# HLK-AX3000-KIT-POWER_LED.net
KiCad netlist of a schematic drawn in Altium Designer
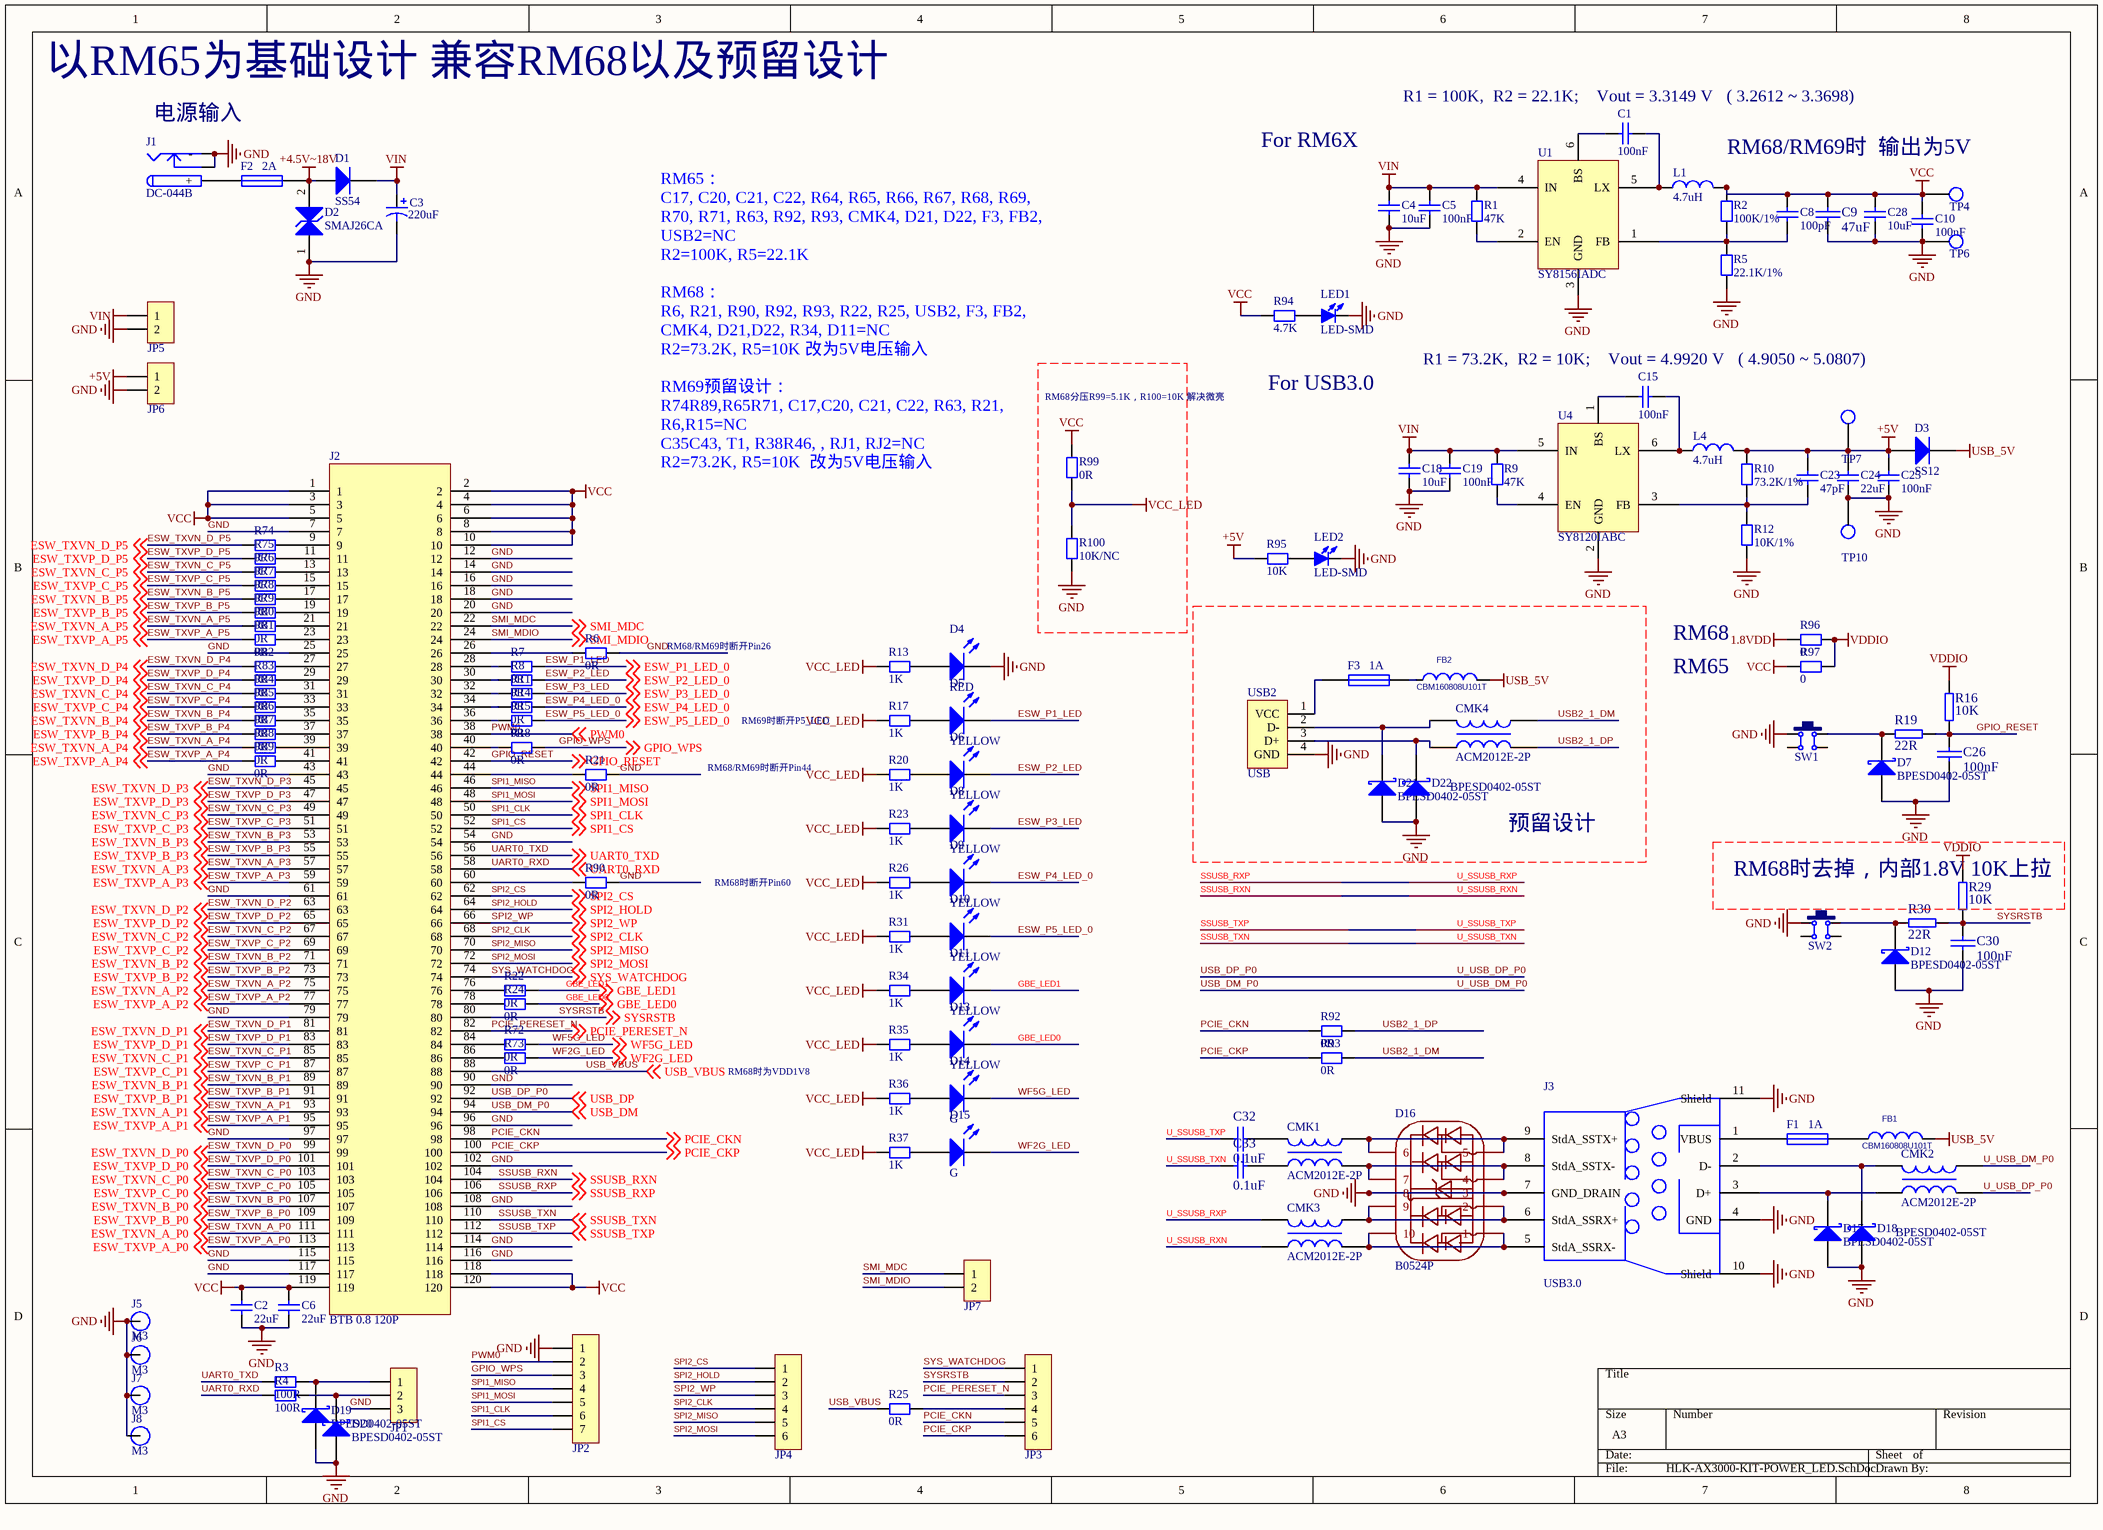
[diagram p0: HLK-AX3000-KIT-POWER_LED.SchDoc]

(export (version "E")
  (design (tool "Eeschema 10.0.6"))
  (components
    (comp (ref "C1")
      (value "100nF")
      (footprint "C 0402_L")
      (description "Capacitor")
      (libsource (lib "LORATEMPSENSOR_V0.02") (part "Cap"))
    )
    (comp (ref "C2")
      (value "22uF")
      (footprint "C 0805_L")
      (description "Capacitor")
      (fields
        (field (name "MANUFACTURER") "Generic Components")
        (field (name "PUBLISHER") "Altium Hobart Technology Centre")
      )
      (libsource (lib "*") (part "Cap"))
    )
    (comp (ref "C3")
      (value "220uF")
      (footprint "CT 8*12 - C")
      (description "Polarized Capacitor (Radial)")
      (fields (field (name "PUBLISHER") "Altium Limited"))
      (libsource (lib "Miscellaneous Devices") (part "Cap Pol1"))
    )
    (comp (ref "C4")
      (value "10uF")
      (footprint "C 0805_L")
      (description "Capacitor")
      (fields
        (field (name "MANUFACTURER") "Generic Components")
        (field (name "PUBLISHER") "Altium Hobart Technology Centre")
      )
      (libsource (lib "*") (part "Cap"))
    )
    (comp (ref "C5")
      (value "100nF")
      (footprint "C 0402_L")
      (description "Capacitor")
      (libsource (lib "LORATEMPSENSOR_V0.02") (part "Cap"))
    )
    (comp (ref "C6")
      (value "22uF")
      (footprint "C 0805_L")
      (description "Capacitor")
      (fields
        (field (name "MANUFACTURER") "Generic Components")
        (field (name "PUBLISHER") "Altium Hobart Technology Centre")
      )
      (libsource (lib "*") (part "Cap"))
    )
    (comp (ref "C8")
      (value "100pF")
      (footprint "C 0402_L")
      (description "Capacitor")
      (fields
        (field (name "MANUFACTURER") "Generic Components")
        (field (name "PUBLISHER") "Altium Hobart Technology Centre")
      )
      (libsource (lib "*") (part "Cap"))
    )
    (comp (ref "C9")
      (value "47uF")
      (footprint "C 1206_L")
      (description "Capacitor")
      (libsource (lib "*") (part "CAP"))
    )
    (comp (ref "C10")
      (value "100nF")
      (footprint "C 0402_L")
      (description "Capacitor")
      (libsource (lib "LORATEMPSENSOR_V0.02") (part "Cap"))
    )
    (comp (ref "C15")
      (value "100nF")
      (footprint "C 0402_L")
      (description "Capacitor")
      (libsource (lib "LORATEMPSENSOR_V0.02") (part "Cap"))
    )
    (comp (ref "C18")
      (value "10uF")
      (footprint "C 0805_L")
      (description "Capacitor")
      (fields
        (field (name "MANUFACTURER") "Generic Components")
        (field (name "PUBLISHER") "Altium Hobart Technology Centre")
      )
      (libsource (lib "*") (part "Cap"))
    )
    (comp (ref "C19")
      (value "100nF")
      (footprint "C 0402_L")
      (description "Capacitor")
      (libsource (lib "LORATEMPSENSOR_V0.02") (part "Cap"))
    )
    (comp (ref "C23")
      (value "47pF")
      (footprint "C 0402_L")
      (description "Capacitor")
      (fields
        (field (name "MANUFACTURER") "Generic Components")
        (field (name "PUBLISHER") "Altium Hobart Technology Centre")
      )
      (libsource (lib "*") (part "Cap"))
    )
    (comp (ref "C24")
      (value "22uF")
      (footprint "C 0805_L")
      (description "Capacitor")
      (fields
        (field (name "MANUFACTURER") "Generic Components")
        (field (name "PUBLISHER") "Altium Hobart Technology Centre")
      )
      (libsource (lib "*") (part "Cap"))
    )
    (comp (ref "C25")
      (value "100nF")
      (footprint "C 0402_L")
      (description "Capacitor")
      (libsource (lib "LORATEMPSENSOR_V0.02") (part "Cap"))
    )
    (comp (ref "C26")
      (value "100nF")
      (footprint "C 0402_L")
      (description "Capacitor")
      (libsource (lib "*") (part "CAP"))
    )
    (comp (ref "C28")
      (value "10uF")
      (footprint "C 0603_L")
      (description "Capacitor")
      (libsource (lib "LORATEMPSENSOR_V0.02") (part "Cap"))
    )
    (comp (ref "C30")
      (value "100nF")
      (footprint "C 0402_L")
      (description "Capacitor")
      (libsource (lib "*") (part "CAP"))
    )
    (comp (ref "C32")
      (value "0.1uF")
      (footprint "C 0402_L")
      (description "Capacitor")
      (libsource (lib "*") (part "CAP"))
    )
    (comp (ref "C33")
      (value "0.1uF")
      (footprint "C 0402_L")
      (description "Capacitor")
      (libsource (lib "*") (part "CAP"))
    )
    (comp (ref "CMK1") (value "ACM2012E-2P") (footprint "SMD_4P") (libsource (lib "*") (part "CMK1")))
    (comp (ref "CMK2") (value "ACM2012E-2P") (footprint "SMD_4P") (libsource (lib "*") (part "CMK1")))
    (comp (ref "CMK3") (value "ACM2012E-2P") (footprint "SMD_4P") (libsource (lib "*") (part "CMK1")))
    (comp (ref "CMK4") (value "ACM2012E-2P") (footprint "SMD_4P_2.1X2.1") (libsource (lib "*") (part "CMK1")))
    (comp (ref "D1")
      (value "SS54")
      (footprint "SMB")
      (description "Default Diode")
      (fields (field (name "PUBLISHER") "Altium Limited"))
      (libsource (lib "Miscellaneous Devices") (part "Diode"))
    )
    (comp (ref "D2") (value "SMAJ26CA") (footprint "DO-214AC") (libsource (lib "My Schlib") (part "TVS")))
    (comp (ref "D3")
      (value "SS12")
      (footprint "SMA")
      (description "Default Diode")
      (fields (field (name "PUBLISHER") "Altium Limited"))
      (libsource (lib "Miscellaneous Devices") (part "Diode"))
    )
    (comp (ref "D4")
      (value "RED")
      (footprint "LED 3MM-R")
      (description "贴片发光二极管")
      (fields (field (name "PUBLISHER") "Altium Limited"))
      (libsource (lib "LORATEMPSENSOR_V0.02") (part "LED0"))
    )
    (comp (ref "D5")
      (value "YELLOW")
      (footprint "LED 3MM-Y")
      (description "贴片发光二极管")
      (fields (field (name "PUBLISHER") "Altium Limited"))
      (libsource (lib "LORATEMPSENSOR_V0.02") (part "LED0"))
    )
    (comp (ref "D6")
      (value "YELLOW")
      (footprint "LED 3MM-Y")
      (description "贴片发光二极管")
      (fields (field (name "PUBLISHER") "Altium Limited"))
      (libsource (lib "LORATEMPSENSOR_V0.02") (part "LED0"))
    )
    (comp (ref "D7")
      (value "BPESD0402-05ST")
      (footprint "esd0402")
      (description "Silicon AF Schottky Diode for High-Speed Switching")
      (fields (field (name "PUBLISHER") "Altium Limited"))
      (libsource (lib "Miscellaneous Devices") (part "Diode BAS70"))
    )
    (comp (ref "D8")
      (value "YELLOW")
      (footprint "LED 3MM-Y")
      (description "贴片发光二极管")
      (fields (field (name "PUBLISHER") "Altium Limited"))
      (libsource (lib "LORATEMPSENSOR_V0.02") (part "LED0"))
    )
    (comp (ref "D9")
      (value "YELLOW")
      (footprint "LED 3MM-Y")
      (description "贴片发光二极管")
      (fields (field (name "PUBLISHER") "Altium Limited"))
      (libsource (lib "LORATEMPSENSOR_V0.02") (part "LED0"))
    )
    (comp (ref "D10")
      (value "YELLOW")
      (footprint "LED 3MM-Y")
      (description "贴片发光二极管")
      (fields (field (name "PUBLISHER") "Altium Limited"))
      (libsource (lib "LORATEMPSENSOR_V0.02") (part "LED0"))
    )
    (comp (ref "D11")
      (value "YELLOW")
      (footprint "LED 3MM-Y")
      (description "贴片发光二极管")
      (fields (field (name "PUBLISHER") "Altium Limited"))
      (libsource (lib "LORATEMPSENSOR_V0.02") (part "LED0"))
    )
    (comp (ref "D12")
      (value "BPESD0402-05ST")
      (footprint "esd0402")
      (description "Silicon AF Schottky Diode for High-Speed Switching")
      (fields (field (name "PUBLISHER") "Altium Limited"))
      (libsource (lib "Miscellaneous Devices") (part "Diode BAS70"))
    )
    (comp (ref "D13")
      (value "YELLOW")
      (footprint "LED 3MM-Y")
      (description "贴片发光二极管")
      (fields (field (name "PUBLISHER") "Altium Limited"))
      (libsource (lib "LORATEMPSENSOR_V0.02") (part "LED0"))
    )
    (comp (ref "D14")
      (value "G")
      (footprint "LED 3MM-G")
      (description "贴片发光二极管")
      (fields (field (name "PUBLISHER") "Altium Limited"))
      (libsource (lib "LORATEMPSENSOR_V0.02") (part "LED0"))
    )
    (comp (ref "D15")
      (value "G")
      (footprint "LED 3MM-G")
      (description "贴片发光二极管")
      (fields (field (name "PUBLISHER") "Altium Limited"))
      (libsource (lib "LORATEMPSENSOR_V0.02") (part "LED0"))
    )
    (comp (ref "D16") (value "B0524P") (footprint "DFN-10") (libsource (lib "MY SCHLIB") (part "B0524P")))
    (comp (ref "D17")
      (value "BPESD0402-05ST")
      (footprint "ESD0402")
      (description "Silicon AF Schottky Diode for High-Speed Switching")
      (fields (field (name "PUBLISHER") "Altium Limited"))
      (libsource (lib "Miscellaneous Devices") (part "Diode BAS70"))
    )
    (comp (ref "D18")
      (value "BPESD0402-05ST")
      (footprint "ESD0402")
      (description "Silicon AF Schottky Diode for High-Speed Switching")
      (fields (field (name "PUBLISHER") "Altium Limited"))
      (libsource (lib "Miscellaneous Devices") (part "Diode BAS70"))
    )
    (comp (ref "D19")
      (value "BPESD0402-05ST")
      (footprint "esd0402")
      (description "Silicon AF Schottky Diode for High-Speed Switching")
      (fields (field (name "PUBLISHER") "Altium Limited"))
      (libsource (lib "Miscellaneous Devices") (part "Diode BAS70"))
    )
    (comp (ref "D20")
      (value "BPESD0402-05ST")
      (footprint "esd0402")
      (description "Silicon AF Schottky Diode for High-Speed Switching")
      (fields (field (name "PUBLISHER") "Altium Limited"))
      (libsource (lib "Miscellaneous Devices") (part "Diode BAS70"))
    )
    (comp (ref "D21")
      (value "BPESD0402-05ST")
      (footprint "ESD0402")
      (description "Silicon AF Schottky Diode for High-Speed Switching")
      (fields (field (name "PUBLISHER") "Altium Limited"))
      (libsource (lib "Miscellaneous Devices") (part "Diode BAS70"))
    )
    (comp (ref "D22")
      (value "BPESD0402-05ST")
      (footprint "ESD0402")
      (description "Silicon AF Schottky Diode for High-Speed Switching")
      (fields (field (name "PUBLISHER") "Altium Limited"))
      (libsource (lib "Miscellaneous Devices") (part "Diode BAS70"))
    )
    (comp (ref "F1")
      (value "1A")
      (footprint "FU 0603")
      (description "Fuse")
      (fields (field (name "PUBLISHER") "Altium Limited"))
      (libsource (lib "Miscellaneous Devices") (part "Fuse 1"))
    )
    (comp (ref "F2")
      (value "2A")
      (footprint "FU 1206")
      (description "Fuse")
      (fields (field (name "PUBLISHER") "Altium Limited"))
      (libsource (lib "Miscellaneous Devices") (part "Fuse 1"))
    )
    (comp (ref "F3")
      (value "1A")
      (footprint "FU 0603")
      (description "Fuse")
      (fields (field (name "PUBLISHER") "Altium Limited"))
      (libsource (lib "Miscellaneous Devices") (part "Fuse 1"))
    )
    (comp (ref "FB1") (value "CBM160808U101T") (footprint "L 0603") (libsource (lib "*") (part "INDUCTOR")))
    (comp (ref "FB2") (value "CBM160808U101T") (footprint "L 0603") (libsource (lib "*") (part "INDUCTOR")))
    (comp (ref "J1")
      (value "DC-044B")
      (footprint "DC-005")
      (description "Low Voltage Power Supply Connector")
      (fields (field (name "PUBLISHER") "Altium Limited"))
      (libsource (lib "封装") (part "DC-044B"))
    )
    (comp (ref "J2")
      (value "BTB 0.8 120P")
      (footprint "HLK-RM65")
      (libsource (lib "4.15 - 板对板连接器") (part "BTB 0.8 120P"))
    )
    (comp (ref "J3")
      (value "USB3.0")
      (footprint "USB3.0-9P-DIP")
      (libsource (lib "MY SCHLIB") (part "USB3.0"))
    )
    (comp (ref "J5")
      (value "M3")
      (footprint "M3 125X200")
      (description "铜柱孔")
      (fields (field (name "版权归属") "源创客"))
      (libsource (lib "15.1 - 定位孔-焊盘") (part "M3"))
    )
    (comp (ref "J6")
      (value "M3")
      (footprint "M3 125X200")
      (description "铜柱孔")
      (fields (field (name "版权归属") "源创客"))
      (libsource (lib "15.1 - 定位孔-焊盘") (part "M3"))
    )
    (comp (ref "J7")
      (value "M3")
      (footprint "M3 125X200")
      (description "铜柱孔")
      (fields (field (name "版权归属") "源创客"))
      (libsource (lib "15.1 - 定位孔-焊盘") (part "M3"))
    )
    (comp (ref "J8")
      (value "M3")
      (footprint "M3 125X200")
      (description "铜柱孔")
      (fields (field (name "版权归属") "源创客"))
      (libsource (lib "15.1 - 定位孔-焊盘") (part "M3"))
    )
    (comp (ref "JP1")
      (value "HDR-1X3")
      (footprint "HDR2.54-LI-3P")
      (description "3P接插件")
      (fields (field (name "版权归属") "源创客"))
      (libsource (lib "4.5   - 接插件-脚距2.54") (part "Header 3"))
    )
    (comp (ref "JP2")
      (value "HDR-1X7")
      (footprint "HDR2.54-LI-7P")
      (description "7P接插件")
      (fields (field (name "版权归属") "源创客"))
      (libsource (lib "4.5   - 接插件-脚距2.54") (part "Header 7"))
    )
    (comp (ref "JP3")
      (value "HDR-1X6")
      (footprint "HDR2.54-LI-6P")
      (description "6P接插件")
      (fields (field (name "版权归属") "源创客"))
      (libsource (lib "4.5   - 接插件-脚距2.54") (part "Header 6"))
    )
    (comp (ref "JP4")
      (value "HDR-1X6")
      (footprint "HDR2.54-LI-6P")
      (description "6P接插件")
      (fields (field (name "版权归属") "源创客"))
      (libsource (lib "4.5   - 接插件-脚距2.54") (part "Header 6"))
    )
    (comp (ref "JP5")
      (value "HDR-1X2")
      (footprint "XH2.54-LI-2P")
      (description "2P接插件")
      (fields (field (name "版权归属") "源创客"))
      (libsource (lib "4.5   - 接插件-脚距2.54") (part "Header 2"))
    )
    (comp (ref "JP6")
      (value "HDR-1X2")
      (footprint "XH2.54-LI-2P")
      (description "2P接插件")
      (fields (field (name "版权归属") "源创客"))
      (libsource (lib "4.5   - 接插件-脚距2.54") (part "Header 2"))
    )
    (comp (ref "JP7")
      (value "HDR-1X2")
      (footprint "HDR2.54-LI-2P")
      (description "2P接插件")
      (fields (field (name "版权归属") "源创客"))
      (libsource (lib "4.5   - 接插件-脚距2.54") (part "Header 2"))
    )
    (comp (ref "L1") (value "4.7uH") (footprint "L 6*6") (libsource (lib "封装") (part "LineInductors")))
    (comp (ref "L4") (value "4.7uH") (footprint "L 4*4") (libsource (lib "封装") (part "LineInductors")))
    (comp (ref "LED1")
      (value "LED-SMD")
      (footprint "LED 0603G-L")
      (description "贴片LED")
      (fields (field (name "版权归属") "源创客"))
      (libsource (lib "9.1   - LED") (part "LED-SMD"))
    )
    (comp (ref "LED2")
      (value "LED-SMD")
      (footprint "LED 0603G-L")
      (description "贴片LED")
      (fields (field (name "版权归属") "源创客"))
      (libsource (lib "9.1   - LED") (part "LED-SMD"))
    )
    (comp (ref "R1")
      (value "47K")
      (footprint "R 0402_L")
      (description "贴片电阻")
      (fields (field (name "版权归属") "源创客"))
      (libsource (lib "3.1   - 电阻-电容-电感") (part "R"))
    )
    (comp (ref "R2")
      (value "100K/1%")
      (footprint "R 0402_L")
      (description "贴片电阻")
      (fields (field (name "版权归属") "源创客"))
      (libsource (lib "3.1   - 电阻-电容-电感") (part "R"))
    )
    (comp (ref "R3")
      (value "100R")
      (footprint "R 0402_L")
      (description "贴片电阻")
      (fields (field (name "版权归属") "源创客"))
      (libsource (lib "3.1   - 电阻-电容-电感") (part "R"))
    )
    (comp (ref "R4")
      (value "100R")
      (footprint "R 0402_L")
      (description "贴片电阻")
      (fields (field (name "版权归属") "源创客"))
      (libsource (lib "3.1   - 电阻-电容-电感") (part "R"))
    )
    (comp (ref "R5")
      (value "22.1K/1%")
      (footprint "R 0402_L")
      (description "贴片电阻")
      (fields (field (name "版权归属") "源创客"))
      (libsource (lib "3.1   - 电阻-电容-电感") (part "R"))
    )
    (comp (ref "R6")
      (value "0R")
      (footprint "R 0402_L")
      (description "贴片电阻")
      (fields (field (name "版权归属") "源创客"))
      (libsource (lib "3.1   - 电阻-电容-电感") (part "R"))
    )
    (comp (ref "R7")
      (value "0R")
      (footprint "R 0402_L")
      (description "贴片电阻")
      (fields (field (name "版权归属") "源创客"))
      (libsource (lib "3.1   - 电阻-电容-电感") (part "R"))
    )
    (comp (ref "R8")
      (value "0R")
      (footprint "R 0402_L")
      (description "贴片电阻")
      (fields (field (name "版权归属") "源创客"))
      (libsource (lib "3.1   - 电阻-电容-电感") (part "R"))
    )
    (comp (ref "R9")
      (value "47K")
      (footprint "R 0402_L")
      (description "贴片电阻")
      (fields (field (name "版权归属") "源创客"))
      (libsource (lib "3.1   - 电阻-电容-电感") (part "R"))
    )
    (comp (ref "R10")
      (value "73.2K/1%")
      (footprint "R 0402_L")
      (description "贴片电阻")
      (fields (field (name "版权归属") "源创客"))
      (libsource (lib "3.1   - 电阻-电容-电感") (part "R"))
    )
    (comp (ref "R11")
      (value "0R")
      (footprint "R 0402_L")
      (description "贴片电阻")
      (fields (field (name "版权归属") "源创客"))
      (libsource (lib "3.1   - 电阻-电容-电感") (part "R"))
    )
    (comp (ref "R12")
      (value "10K/1%")
      (footprint "R 0402_L")
      (description "贴片电阻")
      (fields (field (name "版权归属") "源创客"))
      (libsource (lib "3.1   - 电阻-电容-电感") (part "R"))
    )
    (comp (ref "R13")
      (value "1K")
      (footprint "R 0402_L")
      (description "贴片电阻")
      (fields (field (name "版权归属") "源创客"))
      (libsource (lib "3.1   - 电阻-电容-电感") (part "R"))
    )
    (comp (ref "R14")
      (value "0R")
      (footprint "R 0402_L")
      (description "贴片电阻")
      (fields (field (name "版权归属") "源创客"))
      (libsource (lib "3.1   - 电阻-电容-电感") (part "R"))
    )
    (comp (ref "R15")
      (value "0R")
      (footprint "R 0402_L")
      (description "贴片电阻")
      (fields (field (name "版权归属") "源创客"))
      (libsource (lib "3.1   - 电阻-电容-电感") (part "R"))
    )
    (comp (ref "R16") (value "10K") (footprint "R 0402_l") (libsource (lib "*") (part "RES2")))
    (comp (ref "R17")
      (value "1K")
      (footprint "R 0402_L")
      (description "贴片电阻")
      (fields (field (name "版权归属") "源创客"))
      (libsource (lib "3.1   - 电阻-电容-电感") (part "R"))
    )
    (comp (ref "R18")
      (value "0R")
      (footprint "R 0402_L")
      (description "贴片电阻")
      (fields (field (name "版权归属") "源创客"))
      (libsource (lib "3.1   - 电阻-电容-电感") (part "R"))
    )
    (comp (ref "R19") (value "22R") (footprint "R 0402_l") (libsource (lib "*") (part "RES2")))
    (comp (ref "R20")
      (value "1K")
      (footprint "R 0402_L")
      (description "贴片电阻")
      (fields (field (name "版权归属") "源创客"))
      (libsource (lib "3.1   - 电阻-电容-电感") (part "R"))
    )
    (comp (ref "R21")
      (value "0R")
      (footprint "R 0402_L")
      (description "贴片电阻")
      (fields (field (name "版权归属") "源创客"))
      (libsource (lib "3.1   - 电阻-电容-电感") (part "R"))
    )
    (comp (ref "R22")
      (value "0R")
      (footprint "R 0402_L")
      (description "贴片电阻")
      (fields (field (name "版权归属") "源创客"))
      (libsource (lib "3.1   - 电阻-电容-电感") (part "R"))
    )
    (comp (ref "R23")
      (value "1K")
      (footprint "R 0402_L")
      (description "贴片电阻")
      (fields (field (name "版权归属") "源创客"))
      (libsource (lib "3.1   - 电阻-电容-电感") (part "R"))
    )
    (comp (ref "R24")
      (value "0R")
      (footprint "R 0402_L")
      (description "贴片电阻")
      (fields (field (name "版权归属") "源创客"))
      (libsource (lib "3.1   - 电阻-电容-电感") (part "R"))
    )
    (comp (ref "R25")
      (value "0R")
      (footprint "R 0402_L")
      (description "贴片电阻")
      (fields (field (name "版权归属") "源创客"))
      (libsource (lib "3.1   - 电阻-电容-电感") (part "R"))
    )
    (comp (ref "R26")
      (value "1K")
      (footprint "R 0402_L")
      (description "贴片电阻")
      (fields (field (name "版权归属") "源创客"))
      (libsource (lib "3.1   - 电阻-电容-电感") (part "R"))
    )
    (comp (ref "R29") (value "10K") (footprint "R 0402_l") (libsource (lib "*") (part "RES2")))
    (comp (ref "R30") (value "22R") (footprint "R 0402_l") (libsource (lib "*") (part "RES2")))
    (comp (ref "R31")
      (value "1K")
      (footprint "R 0402_L")
      (description "贴片电阻")
      (fields (field (name "版权归属") "源创客"))
      (libsource (lib "3.1   - 电阻-电容-电感") (part "R"))
    )
    (comp (ref "R34")
      (value "1K")
      (footprint "R 0402_L")
      (description "贴片电阻")
      (fields (field (name "版权归属") "源创客"))
      (libsource (lib "3.1   - 电阻-电容-电感") (part "R"))
    )
    (comp (ref "R35")
      (value "1K")
      (footprint "R 0402_L")
      (description "贴片电阻")
      (fields (field (name "版权归属") "源创客"))
      (libsource (lib "3.1   - 电阻-电容-电感") (part "R"))
    )
    (comp (ref "R36")
      (value "1K")
      (footprint "R 0402_L")
      (description "贴片电阻")
      (fields (field (name "版权归属") "源创客"))
      (libsource (lib "3.1   - 电阻-电容-电感") (part "R"))
    )
    (comp (ref "R37")
      (value "1K")
      (footprint "R 0402_L")
      (description "贴片电阻")
      (fields (field (name "版权归属") "源创客"))
      (libsource (lib "3.1   - 电阻-电容-电感") (part "R"))
    )
    (comp (ref "R72")
      (value "0R")
      (footprint "R 0402_L")
      (description "贴片电阻")
      (fields (field (name "版权归属") "源创客"))
      (libsource (lib "3.1   - 电阻-电容-电感") (part "R"))
    )
    (comp (ref "R73")
      (value "0R")
      (footprint "R 0402_L")
      (description "贴片电阻")
      (fields (field (name "版权归属") "源创客"))
      (libsource (lib "3.1   - 电阻-电容-电感") (part "R"))
    )
    (comp (ref "R74")
      (value "0R")
      (footprint "R 0402_L")
      (description "贴片电阻")
      (fields (field (name "版权归属") "源创客"))
      (libsource (lib "3.1   - 电阻-电容-电感") (part "R"))
    )
    (comp (ref "R75")
      (value "0R")
      (footprint "R 0402_L")
      (description "贴片电阻")
      (fields (field (name "版权归属") "源创客"))
      (libsource (lib "3.1   - 电阻-电容-电感") (part "R"))
    )
    (comp (ref "R76")
      (value "0R")
      (footprint "R 0402_L")
      (description "贴片电阻")
      (fields (field (name "版权归属") "源创客"))
      (libsource (lib "3.1   - 电阻-电容-电感") (part "R"))
    )
    (comp (ref "R77")
      (value "0R")
      (footprint "R 0402_L")
      (description "贴片电阻")
      (fields (field (name "版权归属") "源创客"))
      (libsource (lib "3.1   - 电阻-电容-电感") (part "R"))
    )
    (comp (ref "R78")
      (value "0R")
      (footprint "R 0402_L")
      (description "贴片电阻")
      (fields (field (name "版权归属") "源创客"))
      (libsource (lib "3.1   - 电阻-电容-电感") (part "R"))
    )
    (comp (ref "R79")
      (value "0R")
      (footprint "R 0402_L")
      (description "贴片电阻")
      (fields (field (name "版权归属") "源创客"))
      (libsource (lib "3.1   - 电阻-电容-电感") (part "R"))
    )
    (comp (ref "R80")
      (value "0R")
      (footprint "R 0402_L")
      (description "贴片电阻")
      (fields (field (name "版权归属") "源创客"))
      (libsource (lib "3.1   - 电阻-电容-电感") (part "R"))
    )
    (comp (ref "R81")
      (value "0R")
      (footprint "R 0402_L")
      (description "贴片电阻")
      (fields (field (name "版权归属") "源创客"))
      (libsource (lib "3.1   - 电阻-电容-电感") (part "R"))
    )
    (comp (ref "R82")
      (value "0R")
      (footprint "R 0402_L")
      (description "贴片电阻")
      (fields (field (name "版权归属") "源创客"))
      (libsource (lib "3.1   - 电阻-电容-电感") (part "R"))
    )
    (comp (ref "R83")
      (value "0R")
      (footprint "R 0402_L")
      (description "贴片电阻")
      (fields (field (name "版权归属") "源创客"))
      (libsource (lib "3.1   - 电阻-电容-电感") (part "R"))
    )
    (comp (ref "R84")
      (value "0R")
      (footprint "R 0402_L")
      (description "贴片电阻")
      (fields (field (name "版权归属") "源创客"))
      (libsource (lib "3.1   - 电阻-电容-电感") (part "R"))
    )
    (comp (ref "R85")
      (value "0R")
      (footprint "R 0402_L")
      (description "贴片电阻")
      (fields (field (name "版权归属") "源创客"))
      (libsource (lib "3.1   - 电阻-电容-电感") (part "R"))
    )
    (comp (ref "R86")
      (value "0R")
      (footprint "R 0402_L")
      (description "贴片电阻")
      (fields (field (name "版权归属") "源创客"))
      (libsource (lib "3.1   - 电阻-电容-电感") (part "R"))
    )
    (comp (ref "R87")
      (value "0R")
      (footprint "R 0402_L")
      (description "贴片电阻")
      (fields (field (name "版权归属") "源创客"))
      (libsource (lib "3.1   - 电阻-电容-电感") (part "R"))
    )
    (comp (ref "R88")
      (value "0R")
      (footprint "R 0402_L")
      (description "贴片电阻")
      (fields (field (name "版权归属") "源创客"))
      (libsource (lib "3.1   - 电阻-电容-电感") (part "R"))
    )
    (comp (ref "R89")
      (value "0R")
      (footprint "R 0402_L")
      (description "贴片电阻")
      (fields (field (name "版权归属") "源创客"))
      (libsource (lib "3.1   - 电阻-电容-电感") (part "R"))
    )
    (comp (ref "R90")
      (value "0R")
      (footprint "R 0402_L")
      (description "贴片电阻")
      (fields (field (name "版权归属") "源创客"))
      (libsource (lib "3.1   - 电阻-电容-电感") (part "R"))
    )
    (comp (ref "R92")
      (value "0R")
      (footprint "R 0402_L")
      (description "贴片电阻")
      (fields (field (name "版权归属") "源创客"))
      (libsource (lib "3.1   - 电阻-电容-电感") (part "R"))
    )
    (comp (ref "R93")
      (value "0R")
      (footprint "R 0402_L")
      (description "贴片电阻")
      (fields (field (name "版权归属") "源创客"))
      (libsource (lib "3.1   - 电阻-电容-电感") (part "R"))
    )
    (comp (ref "R94")
      (value "4.7K")
      (footprint "R 0402_L")
      (description "贴片电阻")
      (fields (field (name "版权归属") "源创客"))
      (libsource (lib "3.1   - 电阻-电容-电感") (part "R"))
    )
    (comp (ref "R95")
      (value "10K")
      (footprint "R 0402_L")
      (description "贴片电阻")
      (fields (field (name "版权归属") "源创客"))
      (libsource (lib "3.1   - 电阻-电容-电感") (part "R"))
    )
    (comp (ref "R96")
      (value "0")
      (footprint "R 0402_L")
      (description "贴片电阻")
      (fields (field (name "版权归属") "源创客"))
      (libsource (lib "3.1   - 电阻-电容-电感") (part "R"))
    )
    (comp (ref "R97")
      (value "0")
      (footprint "R 0402_L")
      (description "贴片电阻")
      (fields (field (name "版权归属") "源创客"))
      (libsource (lib "3.1   - 电阻-电容-电感") (part "R"))
    )
    (comp (ref "R99")
      (value "0R")
      (footprint "R 0402_L")
      (description "贴片电阻")
      (fields (field (name "版权归属") "源创客"))
      (libsource (lib "3.1   - 电阻-电容-电感") (part "R"))
    )
    (comp (ref "R100")
      (value "10K/NC")
      (footprint "R 0402_L")
      (description "贴片电阻")
      (fields (field (name "版权归属") "源创客"))
      (libsource (lib "3.1   - 电阻-电容-电感") (part "R"))
    )
    (comp (ref "SW1")
      (value "6x6x5")
      (footprint "TSW DIP-4.5*4.5*3_V")
      (description "直插6x6轻触开关")
      (fields (field (name "版权归属") "源创客"))
      (libsource (lib "5.1   - 按键-开关") (part "TSW DIP-6x6"))
    )
    (comp (ref "SW2")
      (value "6x6x5")
      (footprint "TSW DIP-4.5*4.5*3_V")
      (description "直插6x6轻触开关")
      (fields (field (name "版权归属") "源创客"))
      (libsource (lib "5.1   - 按键-开关") (part "TSW DIP-6x6"))
    )
    (comp (ref "TP4") (value "测试点") (footprint "TEST 1.6") (libsource (lib "15.1 - 定位孔-焊盘") (part "TP")))
    (comp (ref "TP6") (value "测试点") (footprint "TEST 1.6") (libsource (lib "15.1 - 定位孔-焊盘") (part "TP")))
    (comp (ref "TP7") (value "测试点") (footprint "TEST 1.6") (libsource (lib "15.1 - 定位孔-焊盘") (part "TP")))
    (comp (ref "TP10") (value "测试点") (footprint "TEST 1.6") (libsource (lib "15.1 - 定位孔-焊盘") (part "TP")))
    (comp (ref "U1")
      (value "SY8156IADC")
      (footprint "SOT23-6N")
      (libsource (lib "MY SCHLIB") (part "SY8105"))
    )
    (comp (ref "U4")
      (value "SY8120IABC")
      (footprint "SOT23-6N")
      (libsource (lib "MY SCHLIB") (part "SY8201"))
    )
    (comp (ref "USB2")
      (value "USB")
      (footprint "USB-A/S_E")
      (description "USB-A型母接口")
      (fields (field (name "版权归属") "源创客"))
      (libsource (lib "4.1   - 接口类") (part "USB-A/S"))
    )
  )
  (nets
    (net (code "1") (name "+4.5V~18V") (class "Default")
      (node (ref "D1") (pin "1") (pinfunction "A_1") (pintype "passive"))
      (node (ref "D2") (pin "2") (pinfunction "2_2") (pintype "passive"))
      (node (ref "F2") (pin "2") (pinfunction "2_2") (pintype "passive"))
    )
    (net (code "2") (name "+5V") (class "Default")
      (node (ref "C23") (pin "2") (pinfunction "2_2") (pintype "passive"))
      (node (ref "C24") (pin "2") (pinfunction "2_2") (pintype "passive"))
      (node (ref "C25") (pin "1") (pinfunction "1_1") (pintype "passive"))
      (node (ref "D3") (pin "1") (pinfunction "A_1") (pintype "passive"))
      (node (ref "JP6") (pin "1") (pinfunction "1_1") (pintype "passive"))
      (node (ref "L4") (pin "2") (pinfunction "2_2") (pintype "passive"))
      (node (ref "R10") (pin "1") (pinfunction "1_1") (pintype "passive"))
      (node (ref "R95") (pin "2") (pinfunction "2_2") (pintype "passive"))
      (node (ref "TP7") (pin "1") (pintype "passive"))
    )
    (net (code "3") (name "/USB2_1_DM") (class "Default")
      (node (ref "CMK4") (pin "3") (pinfunction "3_3") (pintype "passive"))
      (node (ref "R93") (pin "1") (pinfunction "1_1") (pintype "passive"))
    )
    (net (code "4") (name "/USB2_1_DP") (class "Default")
      (node (ref "CMK4") (pin "4") (pinfunction "4_4") (pintype "passive"))
      (node (ref "R92") (pin "1") (pinfunction "1_1") (pintype "passive"))
    )
    (net (code "5") (name "1.8VDD") (class "Default")
      (node (ref "R96") (pin "2") (pinfunction "2_2") (pintype "passive"))
    )
    (net (code "6") (name "ESW_P1_LED_0") (class "Default")
      (node (ref "D5") (pin "2") (pinfunction "K_2") (pintype "passive"))
      (node (ref "R7") (pin "1") (pinfunction "1_1") (pintype "passive"))
    )
    (net (code "7") (name "ESW_P2_LED_0") (class "Default")
      (node (ref "D6") (pin "2") (pinfunction "K_2") (pintype "passive"))
      (node (ref "R8") (pin "1") (pinfunction "1_1") (pintype "passive"))
    )
    (net (code "8") (name "ESW_P3_LED_0") (class "Default")
      (node (ref "D8") (pin "2") (pinfunction "K_2") (pintype "passive"))
      (node (ref "R11") (pin "1") (pinfunction "1_1") (pintype "passive"))
    )
    (net (code "9") (name "ESW_P4_LED_0") (class "Default")
      (node (ref "D9") (pin "2") (pinfunction "K_2") (pintype "passive"))
      (node (ref "R14") (pin "1") (pinfunction "1_1") (pintype "passive"))
    )
    (net (code "10") (name "ESW_P5_LED_0") (class "Default")
      (node (ref "D10") (pin "2") (pinfunction "K_2") (pintype "passive"))
      (node (ref "R15") (pin "1") (pinfunction "1_1") (pintype "passive"))
    )
    (net (code "11") (name "ESW_TXVN_A_P0") (class "Default")
      (node (ref "J2") (pin "111") (pinfunction "111_111") (pintype "passive"))
    )
    (net (code "12") (name "ESW_TXVN_A_P1") (class "Default")
      (node (ref "J2") (pin "93") (pinfunction "93_93") (pintype "passive"))
    )
    (net (code "13") (name "ESW_TXVN_A_P2") (class "Default")
      (node (ref "J2") (pin "75") (pinfunction "75_75") (pintype "passive"))
    )
    (net (code "14") (name "ESW_TXVN_A_P3") (class "Default")
      (node (ref "J2") (pin "57") (pinfunction "57_57") (pintype "passive"))
    )
    (net (code "15") (name "ESW_TXVN_A_P4") (class "Default")
      (node (ref "R88") (pin "2") (pinfunction "2_2") (pintype "passive"))
    )
    (net (code "16") (name "ESW_TXVN_A_P5") (class "Default")
      (node (ref "R80") (pin "2") (pinfunction "2_2") (pintype "passive"))
    )
    (net (code "17") (name "ESW_TXVN_B_P0") (class "Default")
      (node (ref "J2") (pin "107") (pinfunction "107_107") (pintype "passive"))
    )
    (net (code "18") (name "ESW_TXVN_B_P1") (class "Default")
      (node (ref "J2") (pin "89") (pinfunction "89_89") (pintype "passive"))
    )
    (net (code "19") (name "ESW_TXVN_B_P2") (class "Default")
      (node (ref "J2") (pin "71") (pinfunction "71_71") (pintype "passive"))
    )
    (net (code "20") (name "ESW_TXVN_B_P3") (class "Default")
      (node (ref "J2") (pin "53") (pinfunction "53_53") (pintype "passive"))
    )
    (net (code "21") (name "ESW_TXVN_B_P4") (class "Default")
      (node (ref "R86") (pin "2") (pinfunction "2_2") (pintype "passive"))
    )
    (net (code "22") (name "ESW_TXVN_B_P5") (class "Default")
      (node (ref "R78") (pin "2") (pinfunction "2_2") (pintype "passive"))
    )
    (net (code "23") (name "ESW_TXVN_C_P0") (class "Default")
      (node (ref "J2") (pin "103") (pinfunction "103_103") (pintype "passive"))
    )
    (net (code "24") (name "ESW_TXVN_C_P1") (class "Default")
      (node (ref "J2") (pin "85") (pinfunction "85_85") (pintype "passive"))
    )
    (net (code "25") (name "ESW_TXVN_C_P2") (class "Default")
      (node (ref "J2") (pin "67") (pinfunction "67_67") (pintype "passive"))
    )
    (net (code "26") (name "ESW_TXVN_C_P3") (class "Default")
      (node (ref "J2") (pin "49") (pinfunction "49_49") (pintype "passive"))
    )
    (net (code "27") (name "ESW_TXVN_C_P4") (class "Default")
      (node (ref "R84") (pin "2") (pinfunction "2_2") (pintype "passive"))
    )
    (net (code "28") (name "ESW_TXVN_C_P5") (class "Default")
      (node (ref "R76") (pin "2") (pinfunction "2_2") (pintype "passive"))
    )
    (net (code "29") (name "ESW_TXVN_D_P0") (class "Default")
      (node (ref "J2") (pin "99") (pinfunction "99_99") (pintype "passive"))
    )
    (net (code "30") (name "ESW_TXVN_D_P1") (class "Default")
      (node (ref "J2") (pin "81") (pinfunction "81_81") (pintype "passive"))
    )
    (net (code "31") (name "ESW_TXVN_D_P2") (class "Default")
      (node (ref "J2") (pin "63") (pinfunction "63_63") (pintype "passive"))
    )
    (net (code "32") (name "ESW_TXVN_D_P3") (class "Default")
      (node (ref "J2") (pin "45") (pinfunction "45_45") (pintype "passive"))
    )
    (net (code "33") (name "ESW_TXVN_D_P4") (class "Default")
      (node (ref "R82") (pin "2") (pinfunction "2_2") (pintype "passive"))
    )
    (net (code "34") (name "ESW_TXVN_D_P5") (class "Default")
      (node (ref "R74") (pin "2") (pinfunction "2_2") (pintype "passive"))
    )
    (net (code "35") (name "ESW_TXVP_A_P0") (class "Default")
      (node (ref "J2") (pin "113") (pinfunction "113_113") (pintype "passive"))
    )
    (net (code "36") (name "ESW_TXVP_A_P1") (class "Default")
      (node (ref "J2") (pin "95") (pinfunction "95_95") (pintype "passive"))
    )
    (net (code "37") (name "ESW_TXVP_A_P2") (class "Default")
      (node (ref "J2") (pin "77") (pinfunction "77_77") (pintype "passive"))
    )
    (net (code "38") (name "ESW_TXVP_A_P3") (class "Default")
      (node (ref "J2") (pin "59") (pinfunction "59_59") (pintype "passive"))
    )
    (net (code "39") (name "ESW_TXVP_A_P4") (class "Default")
      (node (ref "R89") (pin "2") (pinfunction "2_2") (pintype "passive"))
    )
    (net (code "40") (name "ESW_TXVP_A_P5") (class "Default")
      (node (ref "R81") (pin "2") (pinfunction "2_2") (pintype "passive"))
    )
    (net (code "41") (name "ESW_TXVP_B_P0") (class "Default")
      (node (ref "J2") (pin "109") (pinfunction "109_109") (pintype "passive"))
    )
    (net (code "42") (name "ESW_TXVP_B_P1") (class "Default")
      (node (ref "J2") (pin "91") (pinfunction "91_91") (pintype "passive"))
    )
    (net (code "43") (name "ESW_TXVP_B_P2") (class "Default")
      (node (ref "J2") (pin "73") (pinfunction "73_73") (pintype "passive"))
    )
    (net (code "44") (name "ESW_TXVP_B_P3") (class "Default")
      (node (ref "J2") (pin "55") (pinfunction "55_55") (pintype "passive"))
    )
    (net (code "45") (name "ESW_TXVP_B_P4") (class "Default")
      (node (ref "R87") (pin "2") (pinfunction "2_2") (pintype "passive"))
    )
    (net (code "46") (name "ESW_TXVP_B_P5") (class "Default")
      (node (ref "R79") (pin "2") (pinfunction "2_2") (pintype "passive"))
    )
    (net (code "47") (name "ESW_TXVP_C_P0") (class "Default")
      (node (ref "J2") (pin "105") (pinfunction "105_105") (pintype "passive"))
    )
    (net (code "48") (name "ESW_TXVP_C_P1") (class "Default")
      (node (ref "J2") (pin "87") (pinfunction "87_87") (pintype "passive"))
    )
    (net (code "49") (name "ESW_TXVP_C_P2") (class "Default")
      (node (ref "J2") (pin "69") (pinfunction "69_69") (pintype "passive"))
    )
    (net (code "50") (name "ESW_TXVP_C_P3") (class "Default")
      (node (ref "J2") (pin "51") (pinfunction "51_51") (pintype "passive"))
    )
    (net (code "51") (name "ESW_TXVP_C_P4") (class "Default")
      (node (ref "R85") (pin "2") (pinfunction "2_2") (pintype "passive"))
    )
    (net (code "52") (name "ESW_TXVP_C_P5") (class "Default")
      (node (ref "R77") (pin "2") (pinfunction "2_2") (pintype "passive"))
    )
    (net (code "53") (name "ESW_TXVP_D_P0") (class "Default")
      (node (ref "J2") (pin "101") (pinfunction "101_101") (pintype "passive"))
    )
    (net (code "54") (name "ESW_TXVP_D_P1") (class "Default")
      (node (ref "J2") (pin "83") (pinfunction "83_83") (pintype "passive"))
    )
    (net (code "55") (name "ESW_TXVP_D_P2") (class "Default")
      (node (ref "J2") (pin "65") (pinfunction "65_65") (pintype "passive"))
    )
    (net (code "56") (name "ESW_TXVP_D_P3") (class "Default")
      (node (ref "J2") (pin "47") (pinfunction "47_47") (pintype "passive"))
    )
    (net (code "57") (name "ESW_TXVP_D_P4") (class "Default")
      (node (ref "R83") (pin "2") (pinfunction "2_2") (pintype "passive"))
    )
    (net (code "58") (name "ESW_TXVP_D_P5") (class "Default")
      (node (ref "R75") (pin "2") (pinfunction "2_2") (pintype "passive"))
    )
    (net (code "59") (name "GBE_LED0") (class "Default")
      (node (ref "D13") (pin "2") (pinfunction "K_2") (pintype "passive"))
      (node (ref "R24") (pin "1") (pinfunction "1_1") (pintype "passive"))
    )
    (net (code "60") (name "GBE_LED1") (class "Default")
      (node (ref "D11") (pin "2") (pinfunction "K_2") (pintype "passive"))
      (node (ref "R22") (pin "1") (pinfunction "1_1") (pintype "passive"))
    )
    (net (code "61") (name "GND") (class "Default")
      (node (ref "C10") (pin "2") (pinfunction "2_2") (pintype "passive"))
      (node (ref "C18") (pin "1") (pinfunction "1_1") (pintype "passive"))
      (node (ref "C19") (pin "2") (pinfunction "2_2") (pintype "passive"))
      (node (ref "C2") (pin "1") (pinfunction "1_1") (pintype "passive"))
      (node (ref "C24") (pin "1") (pinfunction "1_1") (pintype "passive"))
      (node (ref "C25") (pin "2") (pinfunction "2_2") (pintype "passive"))
      (node (ref "C26") (pin "1") (pinfunction "1_1") (pintype "passive"))
      (node (ref "C28") (pin "2") (pinfunction "2_2") (pintype "passive"))
      (node (ref "C3") (pin "2") (pinfunction "2_2") (pintype "passive"))
      (node (ref "C30") (pin "1") (pinfunction "1_1") (pintype "passive"))
      (node (ref "C4") (pin "1") (pinfunction "1_1") (pintype "passive"))
      (node (ref "C5") (pin "2") (pinfunction "2_2") (pintype "passive"))
      (node (ref "C6") (pin "1") (pinfunction "1_1") (pintype "passive"))
      (node (ref "C9") (pin "1") (pinfunction "1_1") (pintype "passive"))
      (node (ref "D12") (pin "1") (pinfunction "A_1") (pintype "passive"))
      (node (ref "D16") (pin "3") (pinfunction "3_3") (pintype "passive"))
      (node (ref "D16") (pin "8") (pinfunction "8_8") (pintype "passive"))
      (node (ref "D17") (pin "1") (pinfunction "A_1") (pintype "passive"))
      (node (ref "D18") (pin "1") (pinfunction "A_1") (pintype "passive"))
      (node (ref "D19") (pin "1") (pinfunction "A_1") (pintype "passive"))
      (node (ref "D2") (pin "1") (pinfunction "1_1") (pintype "passive"))
      (node (ref "D20") (pin "1") (pinfunction "A_1") (pintype "passive"))
      (node (ref "D21") (pin "1") (pinfunction "A_1") (pintype "passive"))
      (node (ref "D22") (pin "1") (pinfunction "A_1") (pintype "passive"))
      (node (ref "D4") (pin "2") (pinfunction "K_2") (pintype "passive"))
      (node (ref "D7") (pin "1") (pinfunction "A_1") (pintype "passive"))
      (node (ref "J1") (pin "2") (pinfunction "-_2") (pintype "passive"))
      (node (ref "J1") (pin "3") (pinfunction "3_3") (pintype "passive"))
      (node (ref "J2") (pin "102") (pinfunction "102_102") (pintype "passive"))
      (node (ref "J2") (pin "108") (pinfunction "108_108") (pintype "passive"))
      (node (ref "J2") (pin "114") (pinfunction "114_114") (pintype "passive"))
      (node (ref "J2") (pin "115") (pinfunction "115_115") (pintype "passive"))
      (node (ref "J2") (pin "116") (pinfunction "116_116") (pintype "passive"))
      (node (ref "J2") (pin "117") (pinfunction "117_117") (pintype "passive"))
      (node (ref "J2") (pin "12") (pinfunction "12_12") (pintype "passive"))
      (node (ref "J2") (pin "14") (pinfunction "14_14") (pintype "passive"))
      (node (ref "J2") (pin "16") (pinfunction "16_16") (pintype "passive"))
      (node (ref "J2") (pin "18") (pinfunction "18_18") (pintype "passive"))
      (node (ref "J2") (pin "20") (pinfunction "20_20") (pintype "passive"))
      (node (ref "J2") (pin "25") (pinfunction "25_25") (pintype "passive"))
      (node (ref "J2") (pin "43") (pinfunction "43_43") (pintype "passive"))
      (node (ref "J2") (pin "54") (pinfunction "54_54") (pintype "passive"))
      (node (ref "J2") (pin "61") (pinfunction "61_61") (pintype "passive"))
      (node (ref "J2") (pin "7") (pinfunction "7_7") (pintype "passive"))
      (node (ref "J2") (pin "79") (pinfunction "79_79") (pintype "passive"))
      (node (ref "J2") (pin "90") (pinfunction "90_90") (pintype "passive"))
      (node (ref "J2") (pin "96") (pinfunction "96_96") (pintype "passive"))
      (node (ref "J2") (pin "97") (pinfunction "97_97") (pintype "passive"))
      (node (ref "J3") (pin "10") (pinfunction "Shield_10") (pintype "passive"))
      (node (ref "J3") (pin "11") (pinfunction "Shield_11") (pintype "passive"))
      (node (ref "J3") (pin "4") (pinfunction "GND_4") (pintype "passive"))
      (node (ref "J3") (pin "7") (pinfunction "GND_DRAIN_7") (pintype "passive"))
      (node (ref "J5") (pin "1") (pinfunction "GND_1") (pintype "passive"))
      (node (ref "J6") (pin "1") (pinfunction "GND_1") (pintype "passive"))
      (node (ref "J7") (pin "1") (pinfunction "GND_1") (pintype "passive"))
      (node (ref "J8") (pin "1") (pinfunction "GND_1") (pintype "passive"))
      (node (ref "JP1") (pin "3") (pinfunction "3_3") (pintype "passive"))
      (node (ref "JP2") (pin "1") (pinfunction "1_1") (pintype "passive"))
      (node (ref "JP5") (pin "2") (pinfunction "2_2") (pintype "passive"))
      (node (ref "JP6") (pin "2") (pinfunction "2_2") (pintype "passive"))
      (node (ref "LED1") (pin "2") (pinfunction "K_2") (pintype "passive"))
      (node (ref "LED2") (pin "2") (pinfunction "K_2") (pintype "passive"))
      (node (ref "R100") (pin "2") (pinfunction "2_2") (pintype "passive"))
      (node (ref "R12") (pin "2") (pinfunction "2_2") (pintype "passive"))
      (node (ref "R21") (pin "1") (pinfunction "1_1") (pintype "passive"))
      (node (ref "R5") (pin "2") (pinfunction "2_2") (pintype "passive"))
      (node (ref "R6") (pin "1") (pinfunction "1_1") (pintype "passive"))
      (node (ref "R90") (pin "1") (pinfunction "1_1") (pintype "passive"))
      (node (ref "SW1") (pin "1") (pinfunction "1_1") (pintype "passive"))
      (node (ref "SW2") (pin "1") (pinfunction "1_1") (pintype "passive"))
      (node (ref "TP10") (pin "1") (pintype "passive"))
      (node (ref "TP6") (pin "1") (pintype "passive"))
      (node (ref "U1") (pin "3") (pinfunction "GND_3") (pintype "passive"))
      (node (ref "U4") (pin "2") (pinfunction "GND_2") (pintype "passive"))
      (node (ref "USB2") (pin "4") (pinfunction "GND_4") (pintype "passive"))
    )
    (net (code "62") (name "GPIO_RESET") (class "Default")
      (node (ref "C26") (pin "2") (pinfunction "2_2") (pintype "passive"))
      (node (ref "J2") (pin "42") (pinfunction "42_42") (pintype "passive"))
      (node (ref "R16") (pin "2") (pinfunction "2_2") (pintype "passive"))
      (node (ref "R19") (pin "2") (pinfunction "2_2") (pintype "passive"))
    )
    (net (code "63") (name "GPIO_WPS") (class "Default")
      (node (ref "JP2") (pin "3") (pinfunction "3_3") (pintype "passive"))
      (node (ref "R18") (pin "1") (pinfunction "1_1") (pintype "passive"))
    )
    (net (code "64") (name "Net-(C32-Pad1)") (class "Default")
      (node (ref "C32") (pin "1") (pinfunction "1_1") (pintype "passive"))
      (node (ref "CMK1") (pin "2") (pinfunction "2_2") (pintype "passive"))
    )
    (net (code "65") (name "Net-(C33-Pad1)") (class "Default")
      (node (ref "C33") (pin "1") (pinfunction "1_1") (pintype "passive"))
      (node (ref "CMK1") (pin "1") (pinfunction "1_1") (pintype "passive"))
    )
    (net (code "66") (name "Net-(D4-A)") (class "Default")
      (node (ref "D4") (pin "1") (pinfunction "A_1") (pintype "passive"))
      (node (ref "R13") (pin "1") (pinfunction "1_1") (pintype "passive"))
    )
    (net (code "67") (name "Net-(D5-A)") (class "Default")
      (node (ref "D5") (pin "1") (pinfunction "A_1") (pintype "passive"))
      (node (ref "R17") (pin "1") (pinfunction "1_1") (pintype "passive"))
    )
    (net (code "68") (name "Net-(D6-A)") (class "Default")
      (node (ref "D6") (pin "1") (pinfunction "A_1") (pintype "passive"))
      (node (ref "R20") (pin "1") (pinfunction "1_1") (pintype "passive"))
    )
    (net (code "69") (name "Net-(D7-K)") (class "Default")
      (node (ref "D7") (pin "2") (pinfunction "K_2") (pintype "passive"))
      (node (ref "R19") (pin "1") (pinfunction "1_1") (pintype "passive"))
      (node (ref "SW1") (pin "2") (pinfunction "2_2") (pintype "passive"))
    )
    (net (code "70") (name "Net-(D8-A)") (class "Default")
      (node (ref "D8") (pin "1") (pinfunction "A_1") (pintype "passive"))
      (node (ref "R23") (pin "1") (pinfunction "1_1") (pintype "passive"))
    )
    (net (code "71") (name "Net-(D9-A)") (class "Default")
      (node (ref "D9") (pin "1") (pinfunction "A_1") (pintype "passive"))
      (node (ref "R26") (pin "1") (pinfunction "1_1") (pintype "passive"))
    )
    (net (code "72") (name "Net-(D10-A)") (class "Default")
      (node (ref "D10") (pin "1") (pinfunction "A_1") (pintype "passive"))
      (node (ref "R31") (pin "1") (pinfunction "1_1") (pintype "passive"))
    )
    (net (code "73") (name "Net-(D11-A)") (class "Default")
      (node (ref "D11") (pin "1") (pinfunction "A_1") (pintype "passive"))
      (node (ref "R34") (pin "1") (pinfunction "1_1") (pintype "passive"))
    )
    (net (code "74") (name "Net-(D12-K)") (class "Default")
      (node (ref "D12") (pin "2") (pinfunction "K_2") (pintype "passive"))
      (node (ref "R30") (pin "1") (pinfunction "1_1") (pintype "passive"))
      (node (ref "SW2") (pin "2") (pinfunction "2_2") (pintype "passive"))
    )
    (net (code "75") (name "Net-(D13-A)") (class "Default")
      (node (ref "D13") (pin "1") (pinfunction "A_1") (pintype "passive"))
      (node (ref "R35") (pin "1") (pinfunction "1_1") (pintype "passive"))
    )
    (net (code "76") (name "Net-(D14-A)") (class "Default")
      (node (ref "D14") (pin "1") (pinfunction "A_1") (pintype "passive"))
      (node (ref "R36") (pin "1") (pinfunction "1_1") (pintype "passive"))
    )
    (net (code "77") (name "Net-(D15-A)") (class "Default")
      (node (ref "D15") (pin "1") (pinfunction "A_1") (pintype "passive"))
      (node (ref "R37") (pin "1") (pinfunction "1_1") (pintype "passive"))
    )
    (net (code "78") (name "Net-(D17-K)") (class "Default")
      (node (ref "CMK2") (pin "1") (pinfunction "1_1") (pintype "passive"))
      (node (ref "D17") (pin "2") (pinfunction "K_2") (pintype "passive"))
      (node (ref "J3") (pin "3") (pinfunction "D+_3") (pintype "passive"))
    )
    (net (code "79") (name "Net-(D18-K)") (class "Default")
      (node (ref "CMK2") (pin "2") (pinfunction "2_2") (pintype "passive"))
      (node (ref "D18") (pin "2") (pinfunction "K_2") (pintype "passive"))
      (node (ref "J3") (pin "2") (pinfunction "D-_2") (pintype "passive"))
    )
    (net (code "80") (name "Net-(D19-K)") (class "Default")
      (node (ref "D19") (pin "2") (pinfunction "K_2") (pintype "passive"))
      (node (ref "JP1") (pin "1") (pinfunction "1_1") (pintype "passive"))
      (node (ref "R3") (pin "1") (pinfunction "1_1") (pintype "passive"))
    )
    (net (code "81") (name "Net-(D20-K)") (class "Default")
      (node (ref "D20") (pin "2") (pinfunction "K_2") (pintype "passive"))
      (node (ref "JP1") (pin "2") (pinfunction "2_2") (pintype "passive"))
      (node (ref "R4") (pin "1") (pinfunction "1_1") (pintype "passive"))
    )
    (net (code "82") (name "Net-(D21-K)") (class "Default")
      (node (ref "CMK4") (pin "2") (pinfunction "2_2") (pintype "passive"))
      (node (ref "D21") (pin "2") (pinfunction "K_2") (pintype "passive"))
      (node (ref "USB2") (pin "2") (pinfunction "D-_2") (pintype "passive"))
    )
    (net (code "83") (name "Net-(D22-K)") (class "Default")
      (node (ref "CMK4") (pin "1") (pinfunction "1_1") (pintype "passive"))
      (node (ref "D22") (pin "2") (pinfunction "K_2") (pintype "passive"))
      (node (ref "USB2") (pin "3") (pinfunction "D+_3") (pintype "passive"))
    )
    (net (code "84") (name "Net-(F1-Pad2)") (class "Default")
      (node (ref "F1") (pin "2") (pinfunction "2_2") (pintype "passive"))
      (node (ref "FB1") (pin "2") (pinfunction "2_2") (pintype "passive"))
    )
    (net (code "85") (name "Net-(F3-Pad2)") (class "Default")
      (node (ref "F3") (pin "2") (pinfunction "2_2") (pintype "passive"))
      (node (ref "FB2") (pin "2") (pinfunction "2_2") (pintype "passive"))
    )
    (net (code "86") (name "Net-(J1-+)") (class "Default")
      (node (ref "F2") (pin "1") (pinfunction "1_1") (pintype "passive"))
      (node (ref "J1") (pin "1") (pinfunction "+_1") (pintype "passive"))
    )
    (net (code "87") (name "Net-(J2-Pad9)") (class "Default")
      (node (ref "J2") (pin "9") (pinfunction "9_9") (pintype "passive"))
      (node (ref "R74") (pin "1") (pinfunction "1_1") (pintype "passive"))
    )
    (net (code "88") (name "Net-(J2-Pad11)") (class "Default")
      (node (ref "J2") (pin "11") (pinfunction "11_11") (pintype "passive"))
      (node (ref "R75") (pin "1") (pinfunction "1_1") (pintype "passive"))
    )
    (net (code "89") (name "Net-(J2-Pad13)") (class "Default")
      (node (ref "J2") (pin "13") (pinfunction "13_13") (pintype "passive"))
      (node (ref "R76") (pin "1") (pinfunction "1_1") (pintype "passive"))
    )
    (net (code "90") (name "Net-(J2-Pad15)") (class "Default")
      (node (ref "J2") (pin "15") (pinfunction "15_15") (pintype "passive"))
      (node (ref "R77") (pin "1") (pinfunction "1_1") (pintype "passive"))
    )
    (net (code "91") (name "Net-(J2-Pad17)") (class "Default")
      (node (ref "J2") (pin "17") (pinfunction "17_17") (pintype "passive"))
      (node (ref "R78") (pin "1") (pinfunction "1_1") (pintype "passive"))
    )
    (net (code "92") (name "Net-(J2-Pad19)") (class "Default")
      (node (ref "J2") (pin "19") (pinfunction "19_19") (pintype "passive"))
      (node (ref "R79") (pin "1") (pinfunction "1_1") (pintype "passive"))
    )
    (net (code "93") (name "Net-(J2-Pad21)") (class "Default")
      (node (ref "J2") (pin "21") (pinfunction "21_21") (pintype "passive"))
      (node (ref "R80") (pin "1") (pinfunction "1_1") (pintype "passive"))
    )
    (net (code "94") (name "Net-(J2-Pad23)") (class "Default")
      (node (ref "J2") (pin "23") (pinfunction "23_23") (pintype "passive"))
      (node (ref "R81") (pin "1") (pinfunction "1_1") (pintype "passive"))
    )
    (net (code "95") (name "Net-(J2-Pad26)") (class "Default")
      (node (ref "J2") (pin "26") (pinfunction "26_26") (pintype "passive"))
      (node (ref "R6") (pin "2") (pinfunction "2_2") (pintype "passive"))
    )
    (net (code "96") (name "Net-(J2-Pad27)") (class "Default")
      (node (ref "J2") (pin "27") (pinfunction "27_27") (pintype "passive"))
      (node (ref "R82") (pin "1") (pinfunction "1_1") (pintype "passive"))
    )
    (net (code "97") (name "Net-(J2-Pad28)") (class "Default")
      (node (ref "J2") (pin "28") (pinfunction "28_28") (pintype "passive"))
      (node (ref "R7") (pin "2") (pinfunction "2_2") (pintype "passive"))
    )
    (net (code "98") (name "Net-(J2-Pad29)") (class "Default")
      (node (ref "J2") (pin "29") (pinfunction "29_29") (pintype "passive"))
      (node (ref "R83") (pin "1") (pinfunction "1_1") (pintype "passive"))
    )
    (net (code "99") (name "Net-(J2-Pad30)") (class "Default")
      (node (ref "J2") (pin "30") (pinfunction "30_30") (pintype "passive"))
      (node (ref "R8") (pin "2") (pinfunction "2_2") (pintype "passive"))
    )
    (net (code "100") (name "Net-(J2-Pad31)") (class "Default")
      (node (ref "J2") (pin "31") (pinfunction "31_31") (pintype "passive"))
      (node (ref "R84") (pin "1") (pinfunction "1_1") (pintype "passive"))
    )
    (net (code "101") (name "Net-(J2-Pad32)") (class "Default")
      (node (ref "J2") (pin "32") (pinfunction "32_32") (pintype "passive"))
      (node (ref "R11") (pin "2") (pinfunction "2_2") (pintype "passive"))
    )
    (net (code "102") (name "Net-(J2-Pad33)") (class "Default")
      (node (ref "J2") (pin "33") (pinfunction "33_33") (pintype "passive"))
      (node (ref "R85") (pin "1") (pinfunction "1_1") (pintype "passive"))
    )
    (net (code "103") (name "Net-(J2-Pad34)") (class "Default")
      (node (ref "J2") (pin "34") (pinfunction "34_34") (pintype "passive"))
      (node (ref "R14") (pin "2") (pinfunction "2_2") (pintype "passive"))
    )
    (net (code "104") (name "Net-(J2-Pad35)") (class "Default")
      (node (ref "J2") (pin "35") (pinfunction "35_35") (pintype "passive"))
      (node (ref "R86") (pin "1") (pinfunction "1_1") (pintype "passive"))
    )
    (net (code "105") (name "Net-(J2-Pad36)") (class "Default")
      (node (ref "J2") (pin "36") (pinfunction "36_36") (pintype "passive"))
      (node (ref "R15") (pin "2") (pinfunction "2_2") (pintype "passive"))
    )
    (net (code "106") (name "Net-(J2-Pad37)") (class "Default")
      (node (ref "J2") (pin "37") (pinfunction "37_37") (pintype "passive"))
      (node (ref "R87") (pin "1") (pinfunction "1_1") (pintype "passive"))
    )
    (net (code "107") (name "Net-(J2-Pad39)") (class "Default")
      (node (ref "J2") (pin "39") (pinfunction "39_39") (pintype "passive"))
      (node (ref "R88") (pin "1") (pinfunction "1_1") (pintype "passive"))
    )
    (net (code "108") (name "Net-(J2-Pad40)") (class "Default")
      (node (ref "J2") (pin "40") (pinfunction "40_40") (pintype "passive"))
      (node (ref "R18") (pin "2") (pinfunction "2_2") (pintype "passive"))
    )
    (net (code "109") (name "Net-(J2-Pad41)") (class "Default")
      (node (ref "J2") (pin "41") (pinfunction "41_41") (pintype "passive"))
      (node (ref "R89") (pin "1") (pinfunction "1_1") (pintype "passive"))
    )
    (net (code "110") (name "Net-(J2-Pad44)") (class "Default")
      (node (ref "J2") (pin "44") (pinfunction "44_44") (pintype "passive"))
      (node (ref "R21") (pin "2") (pinfunction "2_2") (pintype "passive"))
    )
    (net (code "111") (name "Net-(J2-Pad60)") (class "Default")
      (node (ref "J2") (pin "60") (pinfunction "60_60") (pintype "passive"))
      (node (ref "R90") (pin "2") (pinfunction "2_2") (pintype "passive"))
    )
    (net (code "112") (name "Net-(J2-Pad76)") (class "Default")
      (node (ref "J2") (pin "76") (pinfunction "76_76") (pintype "passive"))
      (node (ref "R22") (pin "2") (pinfunction "2_2") (pintype "passive"))
    )
    (net (code "113") (name "Net-(J2-Pad78)") (class "Default")
      (node (ref "J2") (pin "78") (pinfunction "78_78") (pintype "passive"))
      (node (ref "R24") (pin "2") (pinfunction "2_2") (pintype "passive"))
    )
    (net (code "114") (name "Net-(J2-Pad84)") (class "Default")
      (node (ref "J2") (pin "84") (pinfunction "84_84") (pintype "passive"))
      (node (ref "R72") (pin "2") (pinfunction "2_2") (pintype "passive"))
    )
    (net (code "115") (name "Net-(J2-Pad86)") (class "Default")
      (node (ref "J2") (pin "86") (pinfunction "86_86") (pintype "passive"))
      (node (ref "R73") (pin "2") (pinfunction "2_2") (pintype "passive"))
    )
    (net (code "116") (name "Net-(J3-StdA_SSRX+)") (class "Default")
      (node (ref "CMK3") (pin "3") (pinfunction "3_3") (pintype "passive"))
      (node (ref "D16") (pin "2") (pinfunction "2_2") (pintype "passive"))
      (node (ref "D16") (pin "9") (pinfunction "9_9") (pintype "passive"))
      (node (ref "J3") (pin "6") (pinfunction "StdA_SSRX+_6") (pintype "passive"))
    )
    (net (code "117") (name "Net-(J3-StdA_SSRX-)") (class "Default")
      (node (ref "CMK3") (pin "4") (pinfunction "4_4") (pintype "passive"))
      (node (ref "D16") (pin "1") (pinfunction "1_1") (pintype "passive"))
      (node (ref "D16") (pin "10") (pinfunction "10_10") (pintype "passive"))
      (node (ref "J3") (pin "5") (pinfunction "StdA_SSRX-_5") (pintype "passive"))
    )
    (net (code "118") (name "Net-(J3-StdA_SSTX+)") (class "Default")
      (node (ref "CMK1") (pin "3") (pinfunction "3_3") (pintype "passive"))
      (node (ref "D16") (pin "5") (pinfunction "5_5") (pintype "passive"))
      (node (ref "D16") (pin "6") (pinfunction "6_6") (pintype "passive"))
      (node (ref "J3") (pin "9") (pinfunction "StdA_SSTX+_9") (pintype "passive"))
    )
    (net (code "119") (name "Net-(J3-StdA_SSTX-)") (class "Default")
      (node (ref "CMK1") (pin "4") (pinfunction "4_4") (pintype "passive"))
      (node (ref "D16") (pin "4") (pinfunction "4_4") (pintype "passive"))
      (node (ref "D16") (pin "7") (pinfunction "7_7") (pintype "passive"))
      (node (ref "J3") (pin "8") (pinfunction "StdA_SSTX-_8") (pintype "passive"))
    )
    (net (code "120") (name "Net-(J3-VBUS)") (class "Default")
      (node (ref "F1") (pin "1") (pinfunction "1_1") (pintype "passive"))
      (node (ref "J3") (pin "1") (pinfunction "VBUS_1") (pintype "passive"))
    )
    (net (code "121") (name "Net-(JP3-Pad4)") (class "Default")
      (node (ref "JP3") (pin "4") (pinfunction "4_4") (pintype "passive"))
      (node (ref "R25") (pin "1") (pinfunction "1_1") (pintype "passive"))
    )
    (net (code "122") (name "Net-(LED1-A)") (class "Default")
      (node (ref "LED1") (pin "1") (pinfunction "A_1") (pintype "passive"))
      (node (ref "R94") (pin "1") (pinfunction "1_1") (pintype "passive"))
    )
    (net (code "123") (name "Net-(LED2-A)") (class "Default")
      (node (ref "LED2") (pin "1") (pinfunction "A_1") (pintype "passive"))
      (node (ref "R95") (pin "1") (pinfunction "1_1") (pintype "passive"))
    )
    (net (code "124") (name "Net-(U1-BS)") (class "Default")
      (node (ref "C1") (pin "1") (pinfunction "1_1") (pintype "passive"))
      (node (ref "U1") (pin "6") (pinfunction "BS_6") (pintype "passive"))
    )
    (net (code "125") (name "Net-(U1-EN)") (class "Default")
      (node (ref "R1") (pin "2") (pinfunction "2_2") (pintype "passive"))
      (node (ref "U1") (pin "2") (pinfunction "EN_2") (pintype "passive"))
    )
    (net (code "126") (name "Net-(U1-FB)") (class "Default")
      (node (ref "C8") (pin "1") (pinfunction "1_1") (pintype "passive"))
      (node (ref "R2") (pin "2") (pinfunction "2_2") (pintype "passive"))
      (node (ref "R5") (pin "1") (pinfunction "1_1") (pintype "passive"))
      (node (ref "U1") (pin "1") (pinfunction "FB_1") (pintype "passive"))
    )
    (net (code "127") (name "Net-(U1-LX)") (class "Default")
      (node (ref "C1") (pin "2") (pinfunction "2_2") (pintype "passive"))
      (node (ref "L1") (pin "1") (pinfunction "1_1") (pintype "passive"))
      (node (ref "U1") (pin "5") (pinfunction "LX_5") (pintype "passive"))
    )
    (net (code "128") (name "Net-(U4-BS)") (class "Default")
      (node (ref "C15") (pin "1") (pinfunction "1_1") (pintype "passive"))
      (node (ref "U4") (pin "1") (pinfunction "BS_1") (pintype "passive"))
    )
    (net (code "129") (name "Net-(U4-EN)") (class "Default")
      (node (ref "R9") (pin "2") (pinfunction "2_2") (pintype "passive"))
      (node (ref "U4") (pin "4") (pinfunction "EN_4") (pintype "passive"))
    )
    (net (code "130") (name "Net-(U4-FB)") (class "Default")
      (node (ref "C23") (pin "1") (pinfunction "1_1") (pintype "passive"))
      (node (ref "R10") (pin "2") (pinfunction "2_2") (pintype "passive"))
      (node (ref "R12") (pin "1") (pinfunction "1_1") (pintype "passive"))
      (node (ref "U4") (pin "3") (pinfunction "FB_3") (pintype "passive"))
    )
    (net (code "131") (name "Net-(U4-LX)") (class "Default")
      (node (ref "C15") (pin "2") (pinfunction "2_2") (pintype "passive"))
      (node (ref "L4") (pin "1") (pinfunction "1_1") (pintype "passive"))
      (node (ref "U4") (pin "6") (pinfunction "LX_6") (pintype "passive"))
    )
    (net (code "132") (name "Net-(USB2-VCC)") (class "Default")
      (node (ref "F3") (pin "1") (pinfunction "1_1") (pintype "passive"))
      (node (ref "USB2") (pin "1") (pinfunction "VCC_1") (pintype "passive"))
    )
    (net (code "133") (name "PCIE_CKN") (class "Default")
      (node (ref "J2") (pin "98") (pinfunction "98_98") (pintype "passive"))
      (node (ref "JP3") (pin "5") (pinfunction "5_5") (pintype "passive"))
      (node (ref "R92") (pin "2") (pinfunction "2_2") (pintype "passive"))
    )
    (net (code "134") (name "PCIE_CKP") (class "Default")
      (node (ref "J2") (pin "100") (pinfunction "100_100") (pintype "passive"))
      (node (ref "JP3") (pin "6") (pinfunction "6_6") (pintype "passive"))
      (node (ref "R93") (pin "2") (pinfunction "2_2") (pintype "passive"))
    )
    (net (code "135") (name "PCIE_PERESET_N") (class "Default")
      (node (ref "J2") (pin "82") (pinfunction "82_82") (pintype "passive"))
      (node (ref "JP3") (pin "3") (pinfunction "3_3") (pintype "passive"))
    )
    (net (code "136") (name "PWM0") (class "Default")
      (node (ref "J2") (pin "38") (pinfunction "38_38") (pintype "passive"))
      (node (ref "JP2") (pin "2") (pinfunction "2_2") (pintype "passive"))
    )
    (net (code "137") (name "SMI_MDC") (class "Default")
      (node (ref "J2") (pin "22") (pinfunction "22_22") (pintype "passive"))
      (node (ref "JP7") (pin "1") (pinfunction "1_1") (pintype "passive"))
    )
    (net (code "138") (name "SMI_MDIO") (class "Default")
      (node (ref "J2") (pin "24") (pinfunction "24_24") (pintype "passive"))
      (node (ref "JP7") (pin "2") (pinfunction "2_2") (pintype "passive"))
    )
    (net (code "139") (name "SPI1_CLK") (class "Default")
      (node (ref "J2") (pin "50") (pinfunction "50_50") (pintype "passive"))
      (node (ref "JP2") (pin "6") (pinfunction "6_6") (pintype "passive"))
    )
    (net (code "140") (name "SPI1_CS") (class "Default")
      (node (ref "J2") (pin "52") (pinfunction "52_52") (pintype "passive"))
      (node (ref "JP2") (pin "7") (pinfunction "7_7") (pintype "passive"))
    )
    (net (code "141") (name "SPI1_MISO") (class "Default")
      (node (ref "J2") (pin "46") (pinfunction "46_46") (pintype "passive"))
      (node (ref "JP2") (pin "4") (pinfunction "4_4") (pintype "passive"))
    )
    (net (code "142") (name "SPI1_MOSI") (class "Default")
      (node (ref "J2") (pin "48") (pinfunction "48_48") (pintype "passive"))
      (node (ref "JP2") (pin "5") (pinfunction "5_5") (pintype "passive"))
    )
    (net (code "143") (name "SPI2_CLK") (class "Default")
      (node (ref "J2") (pin "68") (pinfunction "68_68") (pintype "passive"))
      (node (ref "JP4") (pin "4") (pinfunction "4_4") (pintype "passive"))
    )
    (net (code "144") (name "SPI2_CS") (class "Default")
      (node (ref "J2") (pin "62") (pinfunction "62_62") (pintype "passive"))
      (node (ref "JP4") (pin "1") (pinfunction "1_1") (pintype "passive"))
    )
    (net (code "145") (name "SPI2_HOLD") (class "Default")
      (node (ref "J2") (pin "64") (pinfunction "64_64") (pintype "passive"))
      (node (ref "JP4") (pin "2") (pinfunction "2_2") (pintype "passive"))
    )
    (net (code "146") (name "SPI2_MISO") (class "Default")
      (node (ref "J2") (pin "70") (pinfunction "70_70") (pintype "passive"))
      (node (ref "JP4") (pin "5") (pinfunction "5_5") (pintype "passive"))
    )
    (net (code "147") (name "SPI2_MOSI") (class "Default")
      (node (ref "J2") (pin "72") (pinfunction "72_72") (pintype "passive"))
      (node (ref "JP4") (pin "6") (pinfunction "6_6") (pintype "passive"))
    )
    (net (code "148") (name "SPI2_WP") (class "Default")
      (node (ref "J2") (pin "66") (pinfunction "66_66") (pintype "passive"))
      (node (ref "JP4") (pin "3") (pinfunction "3_3") (pintype "passive"))
    )
    (net (code "149") (name "SSUSB_RXN") (class "Default")
      (node (ref "CMK3") (pin "1") (pinfunction "1_1") (pintype "passive"))
      (node (ref "J2") (pin "104") (pinfunction "104_104") (pintype "passive"))
    )
    (net (code "150") (name "SSUSB_RXP") (class "Default")
      (node (ref "CMK3") (pin "2") (pinfunction "2_2") (pintype "passive"))
      (node (ref "J2") (pin "106") (pinfunction "106_106") (pintype "passive"))
    )
    (net (code "151") (name "SSUSB_TXN") (class "Default")
      (node (ref "C33") (pin "2") (pinfunction "2_2") (pintype "passive"))
      (node (ref "J2") (pin "110") (pinfunction "110_110") (pintype "passive"))
    )
    (net (code "152") (name "SSUSB_TXP") (class "Default")
      (node (ref "C32") (pin "2") (pinfunction "2_2") (pintype "passive"))
      (node (ref "J2") (pin "112") (pinfunction "112_112") (pintype "passive"))
    )
    (net (code "153") (name "SYSRSTB") (class "Default")
      (node (ref "C30") (pin "2") (pinfunction "2_2") (pintype "passive"))
      (node (ref "J2") (pin "80") (pinfunction "80_80") (pintype "passive"))
      (node (ref "JP3") (pin "2") (pinfunction "2_2") (pintype "passive"))
      (node (ref "R29") (pin "2") (pinfunction "2_2") (pintype "passive"))
      (node (ref "R30") (pin "2") (pinfunction "2_2") (pintype "passive"))
    )
    (net (code "154") (name "SYS_WATCHDOG") (class "Default")
      (node (ref "J2") (pin "74") (pinfunction "74_74") (pintype "passive"))
      (node (ref "JP3") (pin "1") (pinfunction "1_1") (pintype "passive"))
    )
    (net (code "155") (name "UART0_RXD") (class "Default")
      (node (ref "J2") (pin "58") (pinfunction "58_58") (pintype "passive"))
      (node (ref "R4") (pin "2") (pinfunction "2_2") (pintype "passive"))
    )
    (net (code "156") (name "UART0_TXD") (class "Default")
      (node (ref "J2") (pin "56") (pinfunction "56_56") (pintype "passive"))
      (node (ref "R3") (pin "2") (pinfunction "2_2") (pintype "passive"))
    )
    (net (code "157") (name "USB_5V") (class "Default")
      (node (ref "D3") (pin "2") (pinfunction "K_2") (pintype "passive"))
      (node (ref "FB1") (pin "1") (pinfunction "1_1") (pintype "passive"))
      (node (ref "FB2") (pin "1") (pinfunction "1_1") (pintype "passive"))
    )
    (net (code "158") (name "USB_DM") (class "Default")
      (node (ref "CMK2") (pin "3") (pinfunction "3_3") (pintype "passive"))
      (node (ref "J2") (pin "94") (pinfunction "94_94") (pintype "passive"))
    )
    (net (code "159") (name "USB_DP") (class "Default")
      (node (ref "CMK2") (pin "4") (pinfunction "4_4") (pintype "passive"))
      (node (ref "J2") (pin "92") (pinfunction "92_92") (pintype "passive"))
    )
    (net (code "160") (name "USB_VBUS") (class "Default")
      (node (ref "J2") (pin "88") (pinfunction "88_88") (pintype "passive"))
      (node (ref "R25") (pin "2") (pinfunction "2_2") (pintype "passive"))
    )
    (net (code "161") (name "VCC") (class "Default")
      (node (ref "C10") (pin "1") (pinfunction "1_1") (pintype "passive"))
      (node (ref "C2") (pin "2") (pinfunction "2_2") (pintype "passive"))
      (node (ref "C28") (pin "1") (pinfunction "1_1") (pintype "passive"))
      (node (ref "C6") (pin "2") (pinfunction "2_2") (pintype "passive"))
      (node (ref "C8") (pin "2") (pinfunction "2_2") (pintype "passive"))
      (node (ref "C9") (pin "2") (pinfunction "2_2") (pintype "passive"))
      (node (ref "J2") (pin "1") (pinfunction "1_1") (pintype "passive"))
      (node (ref "J2") (pin "10") (pinfunction "10_10") (pintype "passive"))
      (node (ref "J2") (pin "118") (pinfunction "118_118") (pintype "passive"))
      (node (ref "J2") (pin "119") (pinfunction "119_119") (pintype "passive"))
      (node (ref "J2") (pin "120") (pinfunction "120_120") (pintype "passive"))
      (node (ref "J2") (pin "2") (pinfunction "2_2") (pintype "passive"))
      (node (ref "J2") (pin "3") (pinfunction "3_3") (pintype "passive"))
      (node (ref "J2") (pin "4") (pinfunction "4_4") (pintype "passive"))
      (node (ref "J2") (pin "5") (pinfunction "5_5") (pintype "passive"))
      (node (ref "J2") (pin "6") (pinfunction "6_6") (pintype "passive"))
      (node (ref "J2") (pin "8") (pinfunction "8_8") (pintype "passive"))
      (node (ref "L1") (pin "2") (pinfunction "2_2") (pintype "passive"))
      (node (ref "R2") (pin "1") (pinfunction "1_1") (pintype "passive"))
      (node (ref "R94") (pin "2") (pinfunction "2_2") (pintype "passive"))
      (node (ref "R97") (pin "2") (pinfunction "2_2") (pintype "passive"))
      (node (ref "R99") (pin "1") (pinfunction "1_1") (pintype "passive"))
      (node (ref "TP4") (pin "1") (pintype "passive"))
    )
    (net (code "162") (name "VCC_LED") (class "Default")
      (node (ref "R100") (pin "1") (pinfunction "1_1") (pintype "passive"))
      (node (ref "R13") (pin "2") (pinfunction "2_2") (pintype "passive"))
      (node (ref "R17") (pin "2") (pinfunction "2_2") (pintype "passive"))
      (node (ref "R20") (pin "2") (pinfunction "2_2") (pintype "passive"))
      (node (ref "R23") (pin "2") (pinfunction "2_2") (pintype "passive"))
      (node (ref "R26") (pin "2") (pinfunction "2_2") (pintype "passive"))
      (node (ref "R31") (pin "2") (pinfunction "2_2") (pintype "passive"))
      (node (ref "R34") (pin "2") (pinfunction "2_2") (pintype "passive"))
      (node (ref "R35") (pin "2") (pinfunction "2_2") (pintype "passive"))
      (node (ref "R36") (pin "2") (pinfunction "2_2") (pintype "passive"))
      (node (ref "R37") (pin "2") (pinfunction "2_2") (pintype "passive"))
      (node (ref "R99") (pin "2") (pinfunction "2_2") (pintype "passive"))
    )
    (net (code "163") (name "VDDIO") (class "Default")
      (node (ref "R16") (pin "1") (pinfunction "1_1") (pintype "passive"))
      (node (ref "R29") (pin "1") (pinfunction "1_1") (pintype "passive"))
      (node (ref "R96") (pin "1") (pinfunction "1_1") (pintype "passive"))
      (node (ref "R97") (pin "1") (pinfunction "1_1") (pintype "passive"))
    )
    (net (code "164") (name "VIN") (class "Default")
      (node (ref "C18") (pin "2") (pinfunction "2_2") (pintype "passive"))
      (node (ref "C19") (pin "1") (pinfunction "1_1") (pintype "passive"))
      (node (ref "C3") (pin "1") (pinfunction "1_1") (pintype "passive"))
      (node (ref "C4") (pin "2") (pinfunction "2_2") (pintype "passive"))
      (node (ref "C5") (pin "1") (pinfunction "1_1") (pintype "passive"))
      (node (ref "D1") (pin "2") (pinfunction "K_2") (pintype "passive"))
      (node (ref "JP5") (pin "1") (pinfunction "1_1") (pintype "passive"))
      (node (ref "R1") (pin "1") (pinfunction "1_1") (pintype "passive"))
      (node (ref "R9") (pin "1") (pinfunction "1_1") (pintype "passive"))
      (node (ref "U1") (pin "4") (pinfunction "IN_4") (pintype "passive"))
      (node (ref "U4") (pin "5") (pinfunction "IN_5") (pintype "passive"))
    )
    (net (code "165") (name "WF2G_LED") (class "Default")
      (node (ref "D15") (pin "2") (pinfunction "K_2") (pintype "passive"))
      (node (ref "R73") (pin "1") (pinfunction "1_1") (pintype "passive"))
    )
    (net (code "166") (name "WF5G_LED") (class "Default")
      (node (ref "D14") (pin "2") (pinfunction "K_2") (pintype "passive"))
      (node (ref "R72") (pin "1") (pinfunction "1_1") (pintype "passive"))
    )
    (net (code "167") (name "unconnected-(SW1-Pad3)") (class "Default")
      (node (ref "SW1") (pin "3") (pinfunction "3_3") (pintype "passive"))
    )
    (net (code "168") (name "unconnected-(SW1-Pad4)") (class "Default")
      (node (ref "SW1") (pin "4") (pinfunction "4_4") (pintype "passive"))
    )
    (net (code "169") (name "unconnected-(SW2-Pad3)") (class "Default")
      (node (ref "SW2") (pin "3") (pinfunction "3_3") (pintype "passive"))
    )
    (net (code "170") (name "unconnected-(SW2-Pad4)") (class "Default")
      (node (ref "SW2") (pin "4") (pinfunction "4_4") (pintype "passive"))
    )
  )
)
